# p2p-001.net
KiCad netlist of a schematic drawn in EAGLE
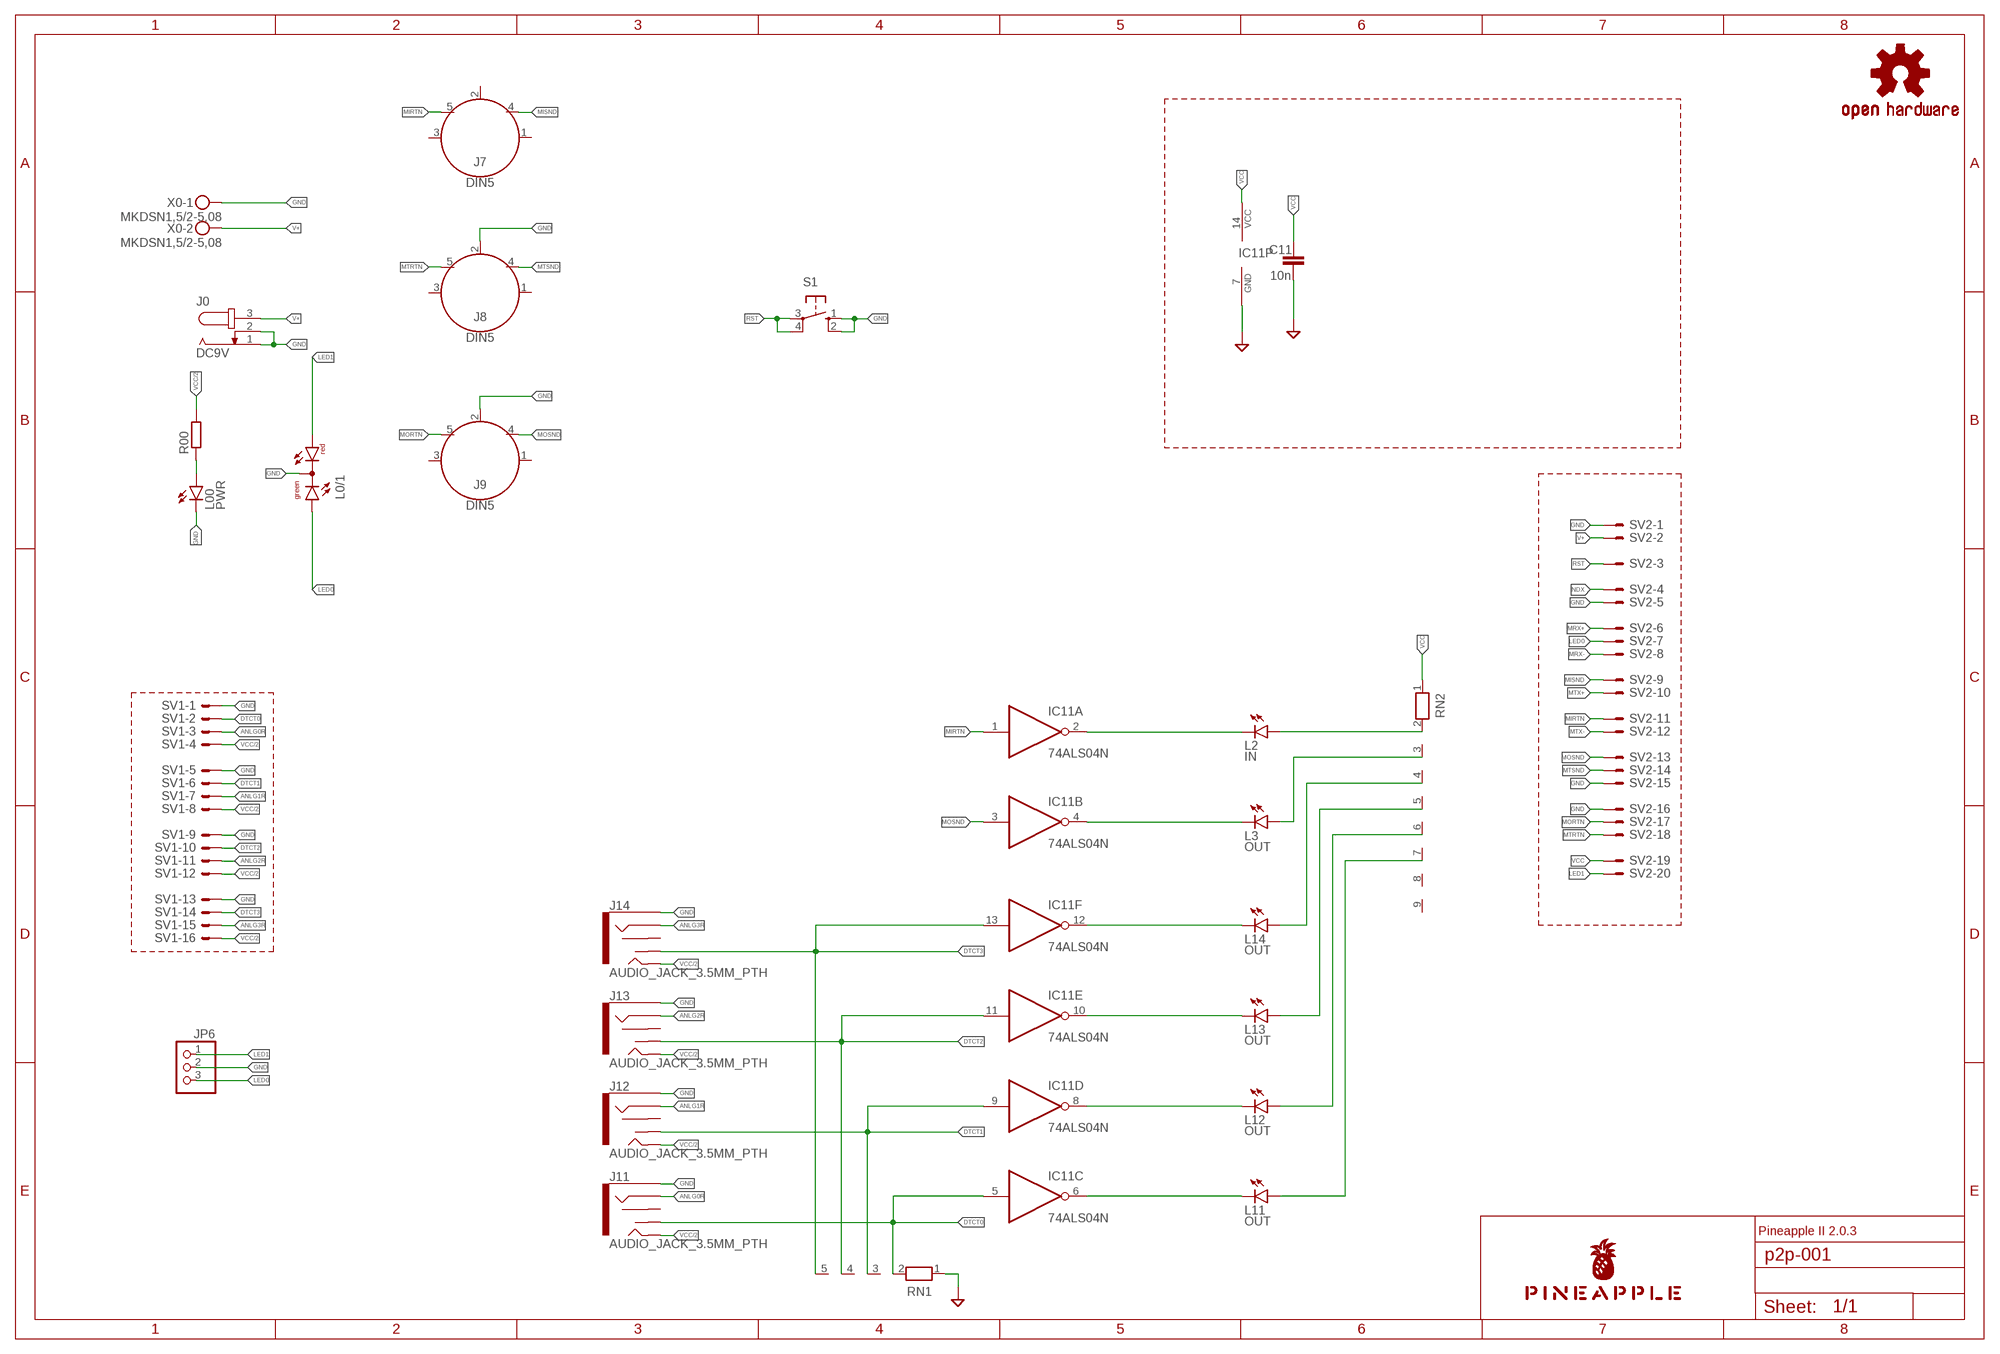
[diagram p0: schematic, sheet 1]

(export (version "E")
  (design (tool "Eeschema 10.0.6"))
  (components
    (comp (ref "C11")
      (value "10n")
      (footprint "eagle-import:C025-024X044")
      (libsource (lib "eagle-import") (part "C-EU025-024X044"))
    )
    (comp (ref "IC11")
      (value "74ALS04N")
      (footprint "eagle-import:DIL14")
      (libsource (lib "eagle-import") (part "7404NALS"))
    )
    (comp (ref "J0")
      (value "DC9V")
      (footprint "eagle-import:SPC4077")
      (libsource (lib "eagle-import") (part "JACK-PLUG0"))
    )
    (comp (ref "J7")
      (value "DIN5")
      (footprint "eagle-import:DIN5-RA-PTH")
      (libsource (lib "eagle-import") (part "DIN5"))
    )
    (comp (ref "J8")
      (value "DIN5")
      (footprint "eagle-import:DIN5-RA-PTH")
      (libsource (lib "eagle-import") (part "DIN5"))
    )
    (comp (ref "J9")
      (value "DIN5")
      (footprint "eagle-import:DIN5-RA-PTH")
      (libsource (lib "eagle-import") (part "DIN5"))
    )
    (comp (ref "J11")
      (value "AUDIO_JACK_3.5MM_PTH")
      (footprint "eagle-import:AUDIO-JACK")
      (libsource (lib "eagle-import") (part "AUDIO_JACK_3.5MM_PTH"))
    )
    (comp (ref "J12")
      (value "AUDIO_JACK_3.5MM_PTH")
      (footprint "eagle-import:AUDIO-JACK")
      (libsource (lib "eagle-import") (part "AUDIO_JACK_3.5MM_PTH"))
    )
    (comp (ref "J13")
      (value "AUDIO_JACK_3.5MM_PTH")
      (footprint "eagle-import:AUDIO-JACK")
      (libsource (lib "eagle-import") (part "AUDIO_JACK_3.5MM_PTH"))
    )
    (comp (ref "J14")
      (value "AUDIO_JACK_3.5MM_PTH")
      (footprint "eagle-import:AUDIO-JACK")
      (libsource (lib "eagle-import") (part "AUDIO_JACK_3.5MM_PTH"))
    )
    (comp (ref "JP6")
      (value "PINHD-1X3")
      (footprint "eagle-import:1X03")
      (libsource (lib "eagle-import") (part "PINHD-1X3"))
    )
    (comp (ref "L00")
      (value "PWR")
      (footprint "eagle-import:LED3MM")
      (libsource (lib "eagle-import") (part "LED3MM"))
    )
    (comp (ref "L0/1")
      (value "DUOLED-RG-C")
      (footprint "eagle-import:DUOLED-C-5MM")
      (libsource (lib "eagle-import") (part "DUOLED-RG-C"))
    )
    (comp (ref "L2")
      (value "IN")
      (footprint "eagle-import:LED3MM")
      (libsource (lib "eagle-import") (part "LED3MM"))
    )
    (comp (ref "L3")
      (value "OUT")
      (footprint "eagle-import:LED3MM")
      (libsource (lib "eagle-import") (part "LED3MM"))
    )
    (comp (ref "L11")
      (value "OUT")
      (footprint "eagle-import:LED3MM")
      (libsource (lib "eagle-import") (part "LED3MM"))
    )
    (comp (ref "L12")
      (value "OUT")
      (footprint "eagle-import:LED3MM")
      (libsource (lib "eagle-import") (part "LED3MM"))
    )
    (comp (ref "L13")
      (value "OUT")
      (footprint "eagle-import:LED3MM")
      (libsource (lib "eagle-import") (part "LED3MM"))
    )
    (comp (ref "L14")
      (value "OUT")
      (footprint "eagle-import:LED3MM")
      (libsource (lib "eagle-import") (part "LED3MM"))
    )
    (comp (ref "LOGO1")
      (value "OSHW-LOGOS-COPPER")
      (footprint "eagle-import:OSHW-LOGO-S_COPPER")
      (libsource (lib "eagle-import") (part "OSHW-LOGOS-COPPER"))
    )
    (comp (ref "R00")
      (value "R-EU_0204/5")
      (footprint "eagle-import:0204_5")
      (libsource (lib "eagle-import") (part "R-EU_0204/5"))
    )
    (comp (ref "RN1")
      (value "RN04")
      (footprint "eagle-import:RN-5")
      (libsource (lib "eagle-import") (part "RN04"))
    )
    (comp (ref "RN2")
      (value "RN08")
      (footprint "eagle-import:RN-9")
      (libsource (lib "eagle-import") (part "RN08"))
    )
    (comp (ref "S1")
      (value "10-XX")
      (footprint "eagle-import:B3F-10XX")
      (fields (field (name "MPN") "B3F-1000"))
      (libsource (lib "eagle-import") (part "10-XX"))
    )
    (comp (ref "SV1")
      (value "ML16LE")
      (footprint "eagle-import:ML16L")
      (libsource (lib "eagle-import") (part "ML16LE"))
    )
    (comp (ref "SV2")
      (value "ML20LE")
      (footprint "eagle-import:ML20L")
      (libsource (lib "eagle-import") (part "ML20LE"))
    )
    (comp (ref "U$1")
      (value "PINEAPPLE450_SILK")
      (footprint "eagle-import:PINEAPPLE450_SILK")
      (libsource (lib "eagle-import") (part "PINEAPPLE450_SILK"))
    )
    (comp (ref "X0")
      (value "MKDSN1,5/2-5,08")
      (footprint "eagle-import:MKDSN1,5_2-5,08")
      (libsource (lib "eagle-import") (part "MKDSN1,5/2-5,08"))
    )
  )
  (nets
    (net (code "1") (name "ANLG0R") (class "Default")
      (node (ref "J11") (pin "RING") (pinfunction "RING_RING") (pintype "bidirectional"))
      (node (ref "SV1") (pin "3") (pinfunction "S_3") (pintype "passive"))
    )
    (net (code "2") (name "ANLG1R") (class "Default")
      (node (ref "J12") (pin "RING") (pinfunction "RING_RING") (pintype "bidirectional"))
      (node (ref "SV1") (pin "7") (pinfunction "S_7") (pintype "passive"))
    )
    (net (code "3") (name "ANLG2R") (class "Default")
      (node (ref "J13") (pin "RING") (pinfunction "RING_RING") (pintype "bidirectional"))
      (node (ref "SV1") (pin "11") (pinfunction "S_11") (pintype "passive"))
    )
    (net (code "4") (name "ANLG3R") (class "Default")
      (node (ref "J14") (pin "RING") (pinfunction "RING_RING") (pintype "bidirectional"))
      (node (ref "SV1") (pin "15") (pinfunction "S_15") (pintype "passive"))
    )
    (net (code "5") (name "DTCT0") (class "Default")
      (node (ref "IC11") (pin "5") (pinfunction "I_5") (pintype "input"))
      (node (ref "J11") (pin "TSH") (pinfunction "TSH_TSH") (pintype "bidirectional"))
      (node (ref "RN1") (pin "2") (pinfunction "2_2") (pintype "passive"))
      (node (ref "SV1") (pin "2") (pinfunction "S_2") (pintype "passive"))
    )
    (net (code "6") (name "DTCT1") (class "Default")
      (node (ref "IC11") (pin "9") (pinfunction "I_9") (pintype "input"))
      (node (ref "J12") (pin "TSH") (pinfunction "TSH_TSH") (pintype "bidirectional"))
      (node (ref "RN1") (pin "3") (pinfunction "3_3") (pintype "passive"))
      (node (ref "SV1") (pin "6") (pinfunction "S_6") (pintype "passive"))
    )
    (net (code "7") (name "DTCT2") (class "Default")
      (node (ref "IC11") (pin "11") (pinfunction "I_11") (pintype "input"))
      (node (ref "J13") (pin "TSH") (pinfunction "TSH_TSH") (pintype "bidirectional"))
      (node (ref "RN1") (pin "4") (pinfunction "4_4") (pintype "passive"))
      (node (ref "SV1") (pin "10") (pinfunction "S_10") (pintype "passive"))
    )
    (net (code "8") (name "DTCT3") (class "Default")
      (node (ref "IC11") (pin "13") (pinfunction "I_13") (pintype "input"))
      (node (ref "J14") (pin "TSH") (pinfunction "TSH_TSH") (pintype "bidirectional"))
      (node (ref "RN1") (pin "5") (pinfunction "5_5") (pintype "passive"))
      (node (ref "SV1") (pin "14") (pinfunction "S_14") (pintype "passive"))
    )
    (net (code "9") (name "GND") (class "Default")
      (node (ref "C11") (pin "2") (pinfunction "2_2") (pintype "passive"))
      (node (ref "IC11") (pin "7") (pinfunction "GND_7") (pintype "power_in"))
      (node (ref "J0") (pin "1") (pinfunction "1_1") (pintype "passive"))
      (node (ref "J0") (pin "2") (pinfunction "2_2") (pintype "passive"))
      (node (ref "J11") (pin "SLEEVE") (pinfunction "SLEEVE_SLEEVE") (pintype "bidirectional"))
      (node (ref "J12") (pin "SLEEVE") (pinfunction "SLEEVE_SLEEVE") (pintype "bidirectional"))
      (node (ref "J13") (pin "SLEEVE") (pinfunction "SLEEVE_SLEEVE") (pintype "bidirectional"))
      (node (ref "J14") (pin "SLEEVE") (pinfunction "SLEEVE_SLEEVE") (pintype "bidirectional"))
      (node (ref "J8") (pin "2") (pinfunction "2_2") (pintype "bidirectional"))
      (node (ref "J9") (pin "2") (pinfunction "2_2") (pintype "bidirectional"))
      (node (ref "JP6") (pin "2") (pinfunction "2_2") (pintype "passive"))
      (node (ref "L0/1") (pin "C") (pinfunction "C_C") (pintype "passive"))
      (node (ref "L00") (pin "K") (pinfunction "C_K") (pintype "passive"))
      (node (ref "RN1") (pin "1") (pinfunction "1_1") (pintype "passive"))
      (node (ref "S1") (pin "1") (pinfunction "S_1") (pintype "passive"))
      (node (ref "S1") (pin "2") (pinfunction "S1_2") (pintype "passive"))
      (node (ref "SV1") (pin "1") (pinfunction "S_1") (pintype "passive"))
      (node (ref "SV1") (pin "13") (pinfunction "S_13") (pintype "passive"))
      (node (ref "SV1") (pin "5") (pinfunction "S_5") (pintype "passive"))
      (node (ref "SV1") (pin "9") (pinfunction "S_9") (pintype "passive"))
      (node (ref "SV2") (pin "1") (pinfunction "S_1") (pintype "passive"))
      (node (ref "SV2") (pin "15") (pinfunction "S_15") (pintype "passive"))
      (node (ref "SV2") (pin "16") (pinfunction "S_16") (pintype "passive"))
      (node (ref "SV2") (pin "5") (pinfunction "S_5") (pintype "passive"))
      (node (ref "X0") (pin "1") (pinfunction "KL_1") (pintype "passive"))
    )
    (net (code "10") (name "LED0") (class "Default")
      (node (ref "JP6") (pin "3") (pinfunction "3_3") (pintype "passive"))
      (node (ref "L0/1") (pin "AX") (pinfunction "AG_AX") (pintype "passive"))
      (node (ref "SV2") (pin "7") (pinfunction "S_7") (pintype "passive"))
    )
    (net (code "11") (name "LED1") (class "Default")
      (node (ref "JP6") (pin "1") (pinfunction "1_1") (pintype "passive"))
      (node (ref "L0/1") (pin "AR") (pinfunction "AR_AR") (pintype "passive"))
      (node (ref "SV2") (pin "20") (pinfunction "S_20") (pintype "passive"))
    )
    (net (code "12") (name "MIRTN") (class "Default")
      (node (ref "IC11") (pin "1") (pinfunction "I_1") (pintype "input"))
      (node (ref "J7") (pin "5") (pinfunction "5_5") (pintype "bidirectional"))
      (node (ref "SV2") (pin "11") (pinfunction "S_11") (pintype "passive"))
    )
    (net (code "13") (name "MISND") (class "Default")
      (node (ref "J7") (pin "4") (pinfunction "4_4") (pintype "bidirectional"))
      (node (ref "SV2") (pin "9") (pinfunction "S_9") (pintype "passive"))
    )
    (net (code "14") (name "MORTN") (class "Default")
      (node (ref "J9") (pin "5") (pinfunction "5_5") (pintype "bidirectional"))
      (node (ref "SV2") (pin "17") (pinfunction "S_17") (pintype "passive"))
    )
    (net (code "15") (name "MOSND") (class "Default")
      (node (ref "IC11") (pin "3") (pinfunction "I_3") (pintype "input"))
      (node (ref "J9") (pin "4") (pinfunction "4_4") (pintype "bidirectional"))
      (node (ref "SV2") (pin "13") (pinfunction "S_13") (pintype "passive"))
    )
    (net (code "16") (name "MRX+") (class "Default")
      (node (ref "SV2") (pin "6") (pinfunction "S_6") (pintype "passive"))
    )
    (net (code "17") (name "MRX-") (class "Default")
      (node (ref "SV2") (pin "8") (pinfunction "S_8") (pintype "passive"))
    )
    (net (code "18") (name "MTRTN") (class "Default")
      (node (ref "J8") (pin "5") (pinfunction "5_5") (pintype "bidirectional"))
      (node (ref "SV2") (pin "18") (pinfunction "S_18") (pintype "passive"))
    )
    (net (code "19") (name "MTSND") (class "Default")
      (node (ref "J8") (pin "4") (pinfunction "4_4") (pintype "bidirectional"))
      (node (ref "SV2") (pin "14") (pinfunction "S_14") (pintype "passive"))
    )
    (net (code "20") (name "MTX+") (class "Default")
      (node (ref "SV2") (pin "10") (pinfunction "S_10") (pintype "passive"))
    )
    (net (code "21") (name "MTX-") (class "Default")
      (node (ref "SV2") (pin "12") (pinfunction "S_12") (pintype "passive"))
    )
    (net (code "22") (name "NDX") (class "Default")
      (node (ref "SV2") (pin "4") (pinfunction "S_4") (pintype "passive"))
    )
    (net (code "23") (name "Net-(IC11A-O)") (class "Default")
      (node (ref "IC11") (pin "2") (pinfunction "O_2") (pintype "output"))
      (node (ref "L2") (pin "K") (pinfunction "C_K") (pintype "passive"))
    )
    (net (code "24") (name "Net-(IC11B-O)") (class "Default")
      (node (ref "IC11") (pin "4") (pinfunction "O_4") (pintype "output"))
      (node (ref "L3") (pin "K") (pinfunction "C_K") (pintype "passive"))
    )
    (net (code "25") (name "Net-(IC11C-O)") (class "Default")
      (node (ref "IC11") (pin "6") (pinfunction "O_6") (pintype "output"))
      (node (ref "L11") (pin "K") (pinfunction "C_K") (pintype "passive"))
    )
    (net (code "26") (name "Net-(IC11D-O)") (class "Default")
      (node (ref "IC11") (pin "8") (pinfunction "O_8") (pintype "output"))
      (node (ref "L12") (pin "K") (pinfunction "C_K") (pintype "passive"))
    )
    (net (code "27") (name "Net-(IC11E-O)") (class "Default")
      (node (ref "IC11") (pin "10") (pinfunction "O_10") (pintype "output"))
      (node (ref "L13") (pin "K") (pinfunction "C_K") (pintype "passive"))
    )
    (net (code "28") (name "Net-(IC11F-O)") (class "Default")
      (node (ref "IC11") (pin "12") (pinfunction "O_12") (pintype "output"))
      (node (ref "L14") (pin "K") (pinfunction "C_K") (pintype "passive"))
    )
    (net (code "29") (name "Net-(L00-PadA)") (class "Default")
      (node (ref "L00") (pin "A") (pinfunction "A_A") (pintype "passive"))
      (node (ref "R00") (pin "1") (pinfunction "1_1") (pintype "passive"))
    )
    (net (code "30") (name "Net-(L2-PadA)") (class "Default")
      (node (ref "L2") (pin "A") (pinfunction "A_A") (pintype "passive"))
      (node (ref "RN2") (pin "2") (pinfunction "2_2") (pintype "passive"))
    )
    (net (code "31") (name "Net-(L3-PadA)") (class "Default")
      (node (ref "L3") (pin "A") (pinfunction "A_A") (pintype "passive"))
      (node (ref "RN2") (pin "3") (pinfunction "3_3") (pintype "passive"))
    )
    (net (code "32") (name "Net-(L11-PadA)") (class "Default")
      (node (ref "L11") (pin "A") (pinfunction "A_A") (pintype "passive"))
      (node (ref "RN2") (pin "7") (pinfunction "7_7") (pintype "passive"))
    )
    (net (code "33") (name "Net-(L12-PadA)") (class "Default")
      (node (ref "L12") (pin "A") (pinfunction "A_A") (pintype "passive"))
      (node (ref "RN2") (pin "6") (pinfunction "6_6") (pintype "passive"))
    )
    (net (code "34") (name "Net-(L13-PadA)") (class "Default")
      (node (ref "L13") (pin "A") (pinfunction "A_A") (pintype "passive"))
      (node (ref "RN2") (pin "5") (pinfunction "5_5") (pintype "passive"))
    )
    (net (code "35") (name "Net-(L14-PadA)") (class "Default")
      (node (ref "L14") (pin "A") (pinfunction "A_A") (pintype "passive"))
      (node (ref "RN2") (pin "4") (pinfunction "4_4") (pintype "passive"))
    )
    (net (code "36") (name "RST") (class "Default")
      (node (ref "S1") (pin "3") (pinfunction "P_3") (pintype "passive"))
      (node (ref "S1") (pin "4") (pinfunction "P1_4") (pintype "passive"))
      (node (ref "SV2") (pin "3") (pinfunction "S_3") (pintype "passive"))
    )
    (net (code "37") (name "V+") (class "Default")
      (node (ref "J0") (pin "3") (pinfunction "3_3") (pintype "passive"))
      (node (ref "SV2") (pin "2") (pinfunction "S_2") (pintype "passive"))
      (node (ref "X0") (pin "2") (pinfunction "KL_2") (pintype "passive"))
    )
    (net (code "38") (name "VCC") (class "Default")
      (node (ref "C11") (pin "1") (pinfunction "1_1") (pintype "passive"))
      (node (ref "IC11") (pin "14") (pinfunction "VCC_14") (pintype "power_in"))
      (node (ref "RN2") (pin "1") (pinfunction "1_1") (pintype "passive"))
      (node (ref "SV2") (pin "19") (pinfunction "S_19") (pintype "passive"))
    )
    (net (code "39") (name "VCC{slash}2") (class "Default")
      (node (ref "J11") (pin "TIP") (pinfunction "TIP_TIP") (pintype "bidirectional"))
      (node (ref "J12") (pin "TIP") (pinfunction "TIP_TIP") (pintype "bidirectional"))
      (node (ref "J13") (pin "TIP") (pinfunction "TIP_TIP") (pintype "bidirectional"))
      (node (ref "J14") (pin "TIP") (pinfunction "TIP_TIP") (pintype "bidirectional"))
      (node (ref "R00") (pin "2") (pinfunction "2_2") (pintype "passive"))
      (node (ref "SV1") (pin "12") (pinfunction "S_12") (pintype "passive"))
      (node (ref "SV1") (pin "16") (pinfunction "S_16") (pintype "passive"))
      (node (ref "SV1") (pin "4") (pinfunction "S_4") (pintype "passive"))
      (node (ref "SV1") (pin "8") (pinfunction "S_8") (pintype "passive"))
    )
    (net (code "40") (name "unconnected-(J7-Pad1)") (class "Default")
      (node (ref "J7") (pin "1") (pinfunction "1_1") (pintype "bidirectional"))
    )
    (net (code "41") (name "unconnected-(J7-Pad2)") (class "Default")
      (node (ref "J7") (pin "2") (pinfunction "2_2") (pintype "bidirectional"))
    )
    (net (code "42") (name "unconnected-(J7-Pad3)") (class "Default")
      (node (ref "J7") (pin "3") (pinfunction "3_3") (pintype "bidirectional"))
    )
    (net (code "43") (name "unconnected-(J8-Pad1)") (class "Default")
      (node (ref "J8") (pin "1") (pinfunction "1_1") (pintype "bidirectional"))
    )
    (net (code "44") (name "unconnected-(J8-Pad3)") (class "Default")
      (node (ref "J8") (pin "3") (pinfunction "3_3") (pintype "bidirectional"))
    )
    (net (code "45") (name "unconnected-(J9-Pad1)") (class "Default")
      (node (ref "J9") (pin "1") (pinfunction "1_1") (pintype "bidirectional"))
    )
    (net (code "46") (name "unconnected-(J9-Pad3)") (class "Default")
      (node (ref "J9") (pin "3") (pinfunction "3_3") (pintype "bidirectional"))
    )
    (net (code "47") (name "unconnected-(J11-PadRSH)") (class "Default")
      (node (ref "J11") (pin "RSH") (pinfunction "RSH_RSH") (pintype "bidirectional"))
    )
    (net (code "48") (name "unconnected-(J12-PadRSH)") (class "Default")
      (node (ref "J12") (pin "RSH") (pinfunction "RSH_RSH") (pintype "bidirectional"))
    )
    (net (code "49") (name "unconnected-(J13-PadRSH)") (class "Default")
      (node (ref "J13") (pin "RSH") (pinfunction "RSH_RSH") (pintype "bidirectional"))
    )
    (net (code "50") (name "unconnected-(J14-PadRSH)") (class "Default")
      (node (ref "J14") (pin "RSH") (pinfunction "RSH_RSH") (pintype "bidirectional"))
    )
    (net (code "51") (name "unconnected-(RN2-Pad8)") (class "Default")
      (node (ref "RN2") (pin "8") (pinfunction "8_8") (pintype "passive"))
    )
    (net (code "52") (name "unconnected-(RN2-Pad9)") (class "Default")
      (node (ref "RN2") (pin "9") (pinfunction "9_9") (pintype "passive"))
    )
  )
)
